# Sheet7.net
KiCad netlist of a schematic drawn in Altium Designer
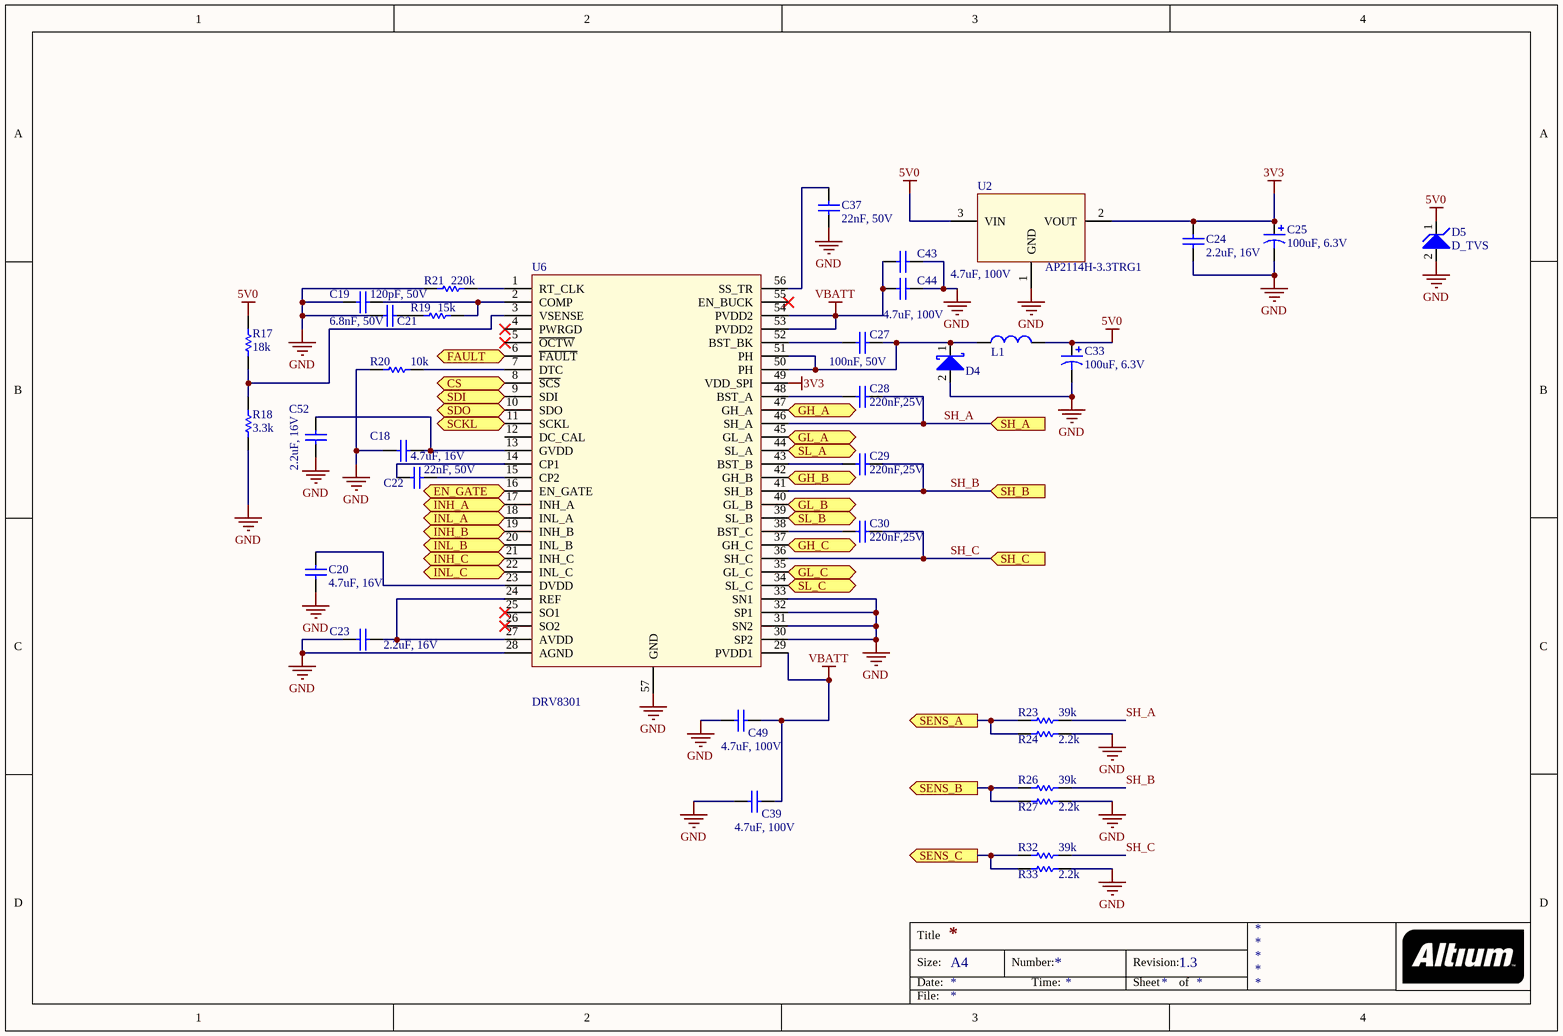
[diagram p0: Sheet7.SchDoc]

(export (version "E")
  (design (tool "Eeschema 10.0.6"))
  (components
    (comp (ref "C18")
      (value "4.7uF, 16V")
      (footprint "SMD-0603 Capacitor")
      (description "CAP 4.7u, 16V, 0603")
      (fields
        (field (name "MANUFACTURER PART NUMBER") "C1608X6S1C475K080AC")
        (field (name "MANUFACTURER") "TDK Corporation")
      )
      (libsource (lib "Master Data Link") (part "CAP"))
    )
    (comp (ref "C19")
      (value "120pF, 50V")
      (footprint "SMD-0603 Capacitor")
      (description "CAP 120p, 50V, 0603")
      (fields
        (field (name "MANUFACTURER PART NUMBER") "GRM39C121J50")
        (field (name "MANUFACTURER") "Murata Electronics North America")
      )
      (libsource (lib "Master Data Link") (part "CAP"))
    )
    (comp (ref "C20")
      (value "4.7uF, 16V")
      (footprint "SMD-0603 Capacitor")
      (description "CAP 4.7u, 16V, 0603")
      (fields
        (field (name "MANUFACTURER PART NUMBER") "C1608X6S1C475K080AC")
        (field (name "MANUFACTURER") "TDK Corporation")
      )
      (libsource (lib "Master Data Link") (part "CAP"))
    )
    (comp (ref "C21")
      (value "6.8nF, 50V")
      (footprint "SMD-0603 Capacitor")
      (description "CAP 6.8n, 50V, 0603")
      (fields
        (field (name "MANUFACTURER PART NUMBER") "GRM18R71H682KA01J")
        (field (name "MANUFACTURER") "Murata Electronics North America")
      )
      (libsource (lib "Master Data Link") (part "CAP"))
    )
    (comp (ref "C22")
      (value "22nF, 50V")
      (footprint "SMD-0603 Capacitor")
      (description "CAP 22n, 50V, 0603")
      (fields
        (field (name "MANUFACTURER PART NUMBER") "GRM18F51H223ZA01D")
        (field (name "MANUFACTURER") "Murata Electronics North America")
      )
      (libsource (lib "Master Data Link") (part "CAP"))
    )
    (comp (ref "C23")
      (value "2.2uF, 16V")
      (footprint "SMD-0603 Capacitor")
      (description "CAP 2.2u, 16V, 0603")
      (fields
        (field (name "MANUFACTURER PART NUMBER") "C1608X5R1C225M")
        (field (name "MANUFACTURER") "TDK Corporation")
      )
      (libsource (lib "Master Data Link") (part "CAP"))
    )
    (comp (ref "C24")
      (value "2.2uF, 16V")
      (footprint "SMD-0603 Capacitor")
      (description "CAP 2.2u, 16V, 0603")
      (fields
        (field (name "MANUFACTURER PART NUMBER") "C1608X5R1C225M")
        (field (name "MANUFACTURER") "TDK Corporation")
      )
      (libsource (lib "Master Data Link") (part "CAP"))
    )
    (comp (ref "C25")
      (value "100uF, 6.3V")
      (footprint "TANT B")
      (description "CAP 100u, 6.3V")
      (fields
        (field (name "MANUFACTURER PART NUMBER") "TPSB107K006R0400")
        (field (name "MANUFACTURER") "AVX Corporation")
      )
      (libsource (lib "Master Data Link") (part "CAP_POL"))
    )
    (comp (ref "C27")
      (value "100nF, 50V")
      (footprint "SMD-0603 Capacitor")
      (description "CAP 100n, 50V, 0603")
      (fields
        (field (name "MANUFACTURER PART NUMBER") "06035C104JAT2A")
        (field (name "MANUFACTURER") "AVX Corporation")
      )
      (libsource (lib "Master Data Link") (part "CAP"))
    )
    (comp (ref "C28")
      (value "220nF,25V")
      (footprint "SMD-0603 Capacitor")
      (description "CAP 220n, 25V, 0603")
      (fields
        (field (name "MANUFACTURER PART NUMBER") "TMK107B7224KA-T")
        (field (name "MANUFACTURER") "Taiyo Yuden")
      )
      (libsource (lib "Master Data Link") (part "CAP"))
    )
    (comp (ref "C29")
      (value "220nF,25V")
      (footprint "SMD-0603 Capacitor")
      (description "CAP 220n, 25V, 0603")
      (fields
        (field (name "MANUFACTURER PART NUMBER") "TMK107B7224KA-T")
        (field (name "MANUFACTURER") "Taiyo Yuden")
      )
      (libsource (lib "Master Data Link") (part "CAP"))
    )
    (comp (ref "C30")
      (value "220nF,25V")
      (footprint "SMD-0603 Capacitor")
      (description "CAP 220n, 25V, 0603")
      (fields
        (field (name "MANUFACTURER PART NUMBER") "TMK107B7224KA-T")
        (field (name "MANUFACTURER") "Taiyo Yuden")
      )
      (libsource (lib "Master Data Link") (part "CAP"))
    )
    (comp (ref "C33")
      (value "100uF, 6.3V")
      (footprint "TANT B")
      (description "CAP 100u, 6.3V")
      (fields
        (field (name "MANUFACTURER PART NUMBER") "TPSB107K006R0400")
        (field (name "MANUFACTURER") "AVX Corporation")
      )
      (libsource (lib "Master Data Link") (part "CAP_POL"))
    )
    (comp (ref "C37")
      (value "22nF, 50V")
      (footprint "SMD-0603 Capacitor")
      (description "CAP 22n, 50V, 0603")
      (fields
        (field (name "MANUFACTURER PART NUMBER") "GRM18F51H223ZA01D")
        (field (name "MANUFACTURER") "Murata Electronics North America")
      )
      (libsource (lib "Master Data Link") (part "CAP"))
    )
    (comp (ref "C39")
      (value "4.7uF, 100V")
      (footprint "SMD-1206 Capacitor")
      (description "4.7µF 100V Ceramic Capacitor X7S 1206")
      (fields
        (field (name "MANUFACTURER PART NUMBER") "12061Z475MAT2A")
        (field (name "MANUFACTURER") "AVX Corporation")
      )
      (libsource (lib "Master Data Link") (part "CAP"))
    )
    (comp (ref "C43")
      (value "4.7uF, 100V")
      (footprint "SMD-1206 Capacitor")
      (description "4.7µF 100V Ceramic Capacitor X7S 1206")
      (fields
        (field (name "MANUFACTURER PART NUMBER") "12061Z475MAT2A")
        (field (name "MANUFACTURER") "AVX Corporation")
      )
      (libsource (lib "Master Data Link") (part "CAP"))
    )
    (comp (ref "C44")
      (value "4.7uF, 100V")
      (footprint "SMD-1206 Capacitor")
      (description "4.7µF 100V Ceramic Capacitor X7S 1206")
      (fields
        (field (name "MANUFACTURER PART NUMBER") "12061Z475MAT2A")
        (field (name "MANUFACTURER") "AVX Corporation")
      )
      (libsource (lib "Master Data Link") (part "CAP"))
    )
    (comp (ref "C49")
      (value "4.7uF, 100V")
      (footprint "SMD-1206 Capacitor")
      (description "4.7µF 100V Ceramic Capacitor X7S 1206")
      (fields
        (field (name "MANUFACTURER PART NUMBER") "12061Z475MAT2A")
        (field (name "MANUFACTURER") "AVX Corporation")
      )
      (libsource (lib "Master Data Link") (part "CAP"))
    )
    (comp (ref "C52")
      (value "2.2uF, 16V")
      (footprint "SMD-0603 Capacitor")
      (description "CAP 2.2u, 16V, 0603")
      (fields
        (field (name "MANUFACTURER PART NUMBER") "C1608X5R1C225M")
        (field (name "MANUFACTURER") "TDK Corporation")
      )
      (libsource (lib "Master Data Link") (part "CAP"))
    )
    (comp (ref "D4")
      (value "Voltage and current important")
      (footprint "SOD-123W")
      (description "Shottky 60V 2A")
      (fields
        (field (name "MANUFACTURER PART NUMBER") "PMEG6020ER-115")
        (field (name "MANUFACTURER") "NXP Semiconductors")
      )
      (libsource (lib "Master Data Link") (part "D_SCHOTTKY"))
    )
    (comp (ref "D5")
      (value "D_TVS")
      (footprint "DO-214AC")
      (description "TVS diode 5V")
      (fields
        (field (name "MANUFACTURER PART NUMBER") "SMAJ5.0A")
        (field (name "MANUFACTURER") "Littelfuse Inc.")
      )
      (libsource (lib "Master Data Link") (part "D_TVS"))
    )
    (comp (ref "L1")
      (value "COIL")
      (footprint "HCM0503")
      (description "FIXED IND 22UH 1.9A 270 MOHM SMD")
      (fields (field (name "MANUFACTURER PART NUMBER") "HCM0503-220-R") (field (name "MANUFACTURER") "Eaton"))
      (libsource (lib "Master Data Link") (part "COIL"))
    )
    (comp (ref "R17")
      (value "18k")
      (footprint "SMD-0603 Resistor")
      (description "R 18k, 0603")
      (fields
        (field (name "MANUFACTURER PART NUMBER") "RK73H1JTTD1802F")
        (field (name "MANUFACTURER") "KOA Speer")
      )
      (libsource (lib "Master Data Link") (part "RES"))
    )
    (comp (ref "R18")
      (value "3.3k")
      (footprint "SMD-0603 Resistor")
      (description "R 3.3k, 0603")
      (fields
        (field (name "MANUFACTURER PART NUMBER") "RK73H1JTTD3301F")
        (field (name "MANUFACTURER") "KOA Speer")
      )
      (libsource (lib "Master Data Link") (part "RES"))
    )
    (comp (ref "R19")
      (value "15k")
      (footprint "SMD-0603 Resistor")
      (description "R 15k, 0603")
      (fields
        (field (name "MANUFACTURER PART NUMBER") "RK73H1JTTD1502F")
        (field (name "MANUFACTURER") "KOA Speer")
      )
      (libsource (lib "Master Data Link") (part "RES"))
    )
    (comp (ref "R20")
      (value "10k")
      (footprint "SMD-0603 Resistor")
      (description "R 10k, 0603")
      (fields
        (field (name "MANUFACTURER PART NUMBER") "RK73H1JTTD1002F")
        (field (name "MANUFACTURER") "KOA Speer")
      )
      (libsource (lib "Master Data Link") (part "RES"))
    )
    (comp (ref "R21")
      (value "220k")
      (footprint "SMD-0603 Resistor")
      (description "R 220k, 0603")
      (fields
        (field (name "MANUFACTURER PART NUMBER") "RK73H1JTTD2203F")
        (field (name "MANUFACTURER") "KOA Speer")
      )
      (libsource (lib "Master Data Link") (part "RES"))
    )
    (comp (ref "R23")
      (value "39k")
      (footprint "SMD-0603 Resistor")
      (description "R 39k, 0603")
      (fields
        (field (name "MANUFACTURER PART NUMBER") "ERJ-3EKF3902V")
        (field (name "MANUFACTURER") "Panasonic Electronic Components")
      )
      (libsource (lib "Master Data Link") (part "RES"))
    )
    (comp (ref "R24")
      (value "2.2k")
      (footprint "SMD-0603 Resistor")
      (description "R 2.2k, 0603")
      (fields
        (field (name "MANUFACTURER PART NUMBER") "RK73H1JTTD2201F")
        (field (name "MANUFACTURER") "KOA Speer")
      )
      (libsource (lib "Master Data Link") (part "RES"))
    )
    (comp (ref "R26")
      (value "39k")
      (footprint "SMD-0603 Resistor")
      (description "R 39k, 0603")
      (fields
        (field (name "MANUFACTURER PART NUMBER") "ERJ-3EKF3902V")
        (field (name "MANUFACTURER") "Panasonic Electronic Components")
      )
      (libsource (lib "Master Data Link") (part "RES"))
    )
    (comp (ref "R27")
      (value "2.2k")
      (footprint "SMD-0603 Resistor")
      (description "R 2.2k, 0603")
      (fields
        (field (name "MANUFACTURER PART NUMBER") "RK73H1JTTD2201F")
        (field (name "MANUFACTURER") "KOA Speer")
      )
      (libsource (lib "Master Data Link") (part "RES"))
    )
    (comp (ref "R32")
      (value "39k")
      (footprint "SMD-0603 Resistor")
      (description "R 39k, 0603")
      (fields
        (field (name "MANUFACTURER PART NUMBER") "ERJ-3EKF3902V")
        (field (name "MANUFACTURER") "Panasonic Electronic Components")
      )
      (libsource (lib "Master Data Link") (part "RES"))
    )
    (comp (ref "R33")
      (value "2.2k")
      (footprint "SMD-0603 Resistor")
      (description "R 2.2k, 0603")
      (fields
        (field (name "MANUFACTURER PART NUMBER") "RK73H1JTTD2201F")
        (field (name "MANUFACTURER") "KOA Speer")
      )
      (libsource (lib "Master Data Link") (part "RES"))
    )
    (comp (ref "U2")
      (value "3.3V")
      (footprint "SOT230P700X180-4N")
      (description "VREG LDO")
      (fields
        (field (name "MANUFACTURER PART NUMBER") "AP2114H-3.3TRG1")
        (field (name "MANUFACTURER") "Diodes Incorporated")
      )
      (libsource (lib "Master Data Link") (part "VREG_LDO"))
    )
    (comp (ref "U6")
      (value "DRV8301")
      (footprint "SOP127P600-8N")
      (description "IC MOTOR CONTROLLER SPI 56HTSSOP")
      (fields
        (field (name "MANUFACTURER PART NUMBER") "DRV8301DCA")
        (field (name "MANUFACTURER") "Texas Instruments")
      )
      (libsource (lib "Master Data Link") (part "DRV8301"))
    )
  )
  (nets
    (net (code "1") (name "/CS") (class "Default")
      (node (ref "U6") (pin "8") (pinfunction "~{SCS}_8") (pintype "passive"))
    )
    (net (code "2") (name "/EN_GATE") (class "Default")
      (node (ref "U6") (pin "16") (pinfunction "EN_GATE_16") (pintype "passive"))
    )
    (net (code "3") (name "/FAULT") (class "Default")
      (node (ref "U6") (pin "6") (pinfunction "~{FAULT}_6") (pintype "passive"))
    )
    (net (code "4") (name "/GH_A") (class "Default")
      (node (ref "U6") (pin "47") (pinfunction "GH_A_47") (pintype "passive"))
    )
    (net (code "5") (name "/GH_B") (class "Default")
      (node (ref "U6") (pin "42") (pinfunction "GH_B_42") (pintype "passive"))
    )
    (net (code "6") (name "/GH_C") (class "Default")
      (node (ref "U6") (pin "37") (pinfunction "GH_C_37") (pintype "passive"))
    )
    (net (code "7") (name "/GL_A") (class "Default")
      (node (ref "U6") (pin "45") (pinfunction "GL_A_45") (pintype "passive"))
    )
    (net (code "8") (name "/GL_B") (class "Default")
      (node (ref "U6") (pin "40") (pinfunction "GL_B_40") (pintype "passive"))
    )
    (net (code "9") (name "/GL_C") (class "Default")
      (node (ref "U6") (pin "35") (pinfunction "GL_C_35") (pintype "passive"))
    )
    (net (code "10") (name "/INH_A") (class "Default")
      (node (ref "U6") (pin "17") (pinfunction "INH_A_17") (pintype "passive"))
    )
    (net (code "11") (name "/INH_B") (class "Default")
      (node (ref "U6") (pin "19") (pinfunction "INH_B_19") (pintype "passive"))
    )
    (net (code "12") (name "/INH_C") (class "Default")
      (node (ref "U6") (pin "21") (pinfunction "INH_C_21") (pintype "passive"))
    )
    (net (code "13") (name "/INL_A") (class "Default")
      (node (ref "U6") (pin "18") (pinfunction "INL_A_18") (pintype "passive"))
    )
    (net (code "14") (name "/INL_B") (class "Default")
      (node (ref "U6") (pin "20") (pinfunction "INL_B_20") (pintype "passive"))
    )
    (net (code "15") (name "/INL_C") (class "Default")
      (node (ref "U6") (pin "22") (pinfunction "INL_C_22") (pintype "passive"))
    )
    (net (code "16") (name "/SCKL") (class "Default")
      (node (ref "U6") (pin "11") (pinfunction "SCKL_11") (pintype "passive"))
    )
    (net (code "17") (name "/SDI") (class "Default")
      (node (ref "U6") (pin "9") (pinfunction "SDI_9") (pintype "passive"))
    )
    (net (code "18") (name "/SDO") (class "Default")
      (node (ref "U6") (pin "10") (pinfunction "SDO_10") (pintype "passive"))
    )
    (net (code "19") (name "/SENS_A") (class "Default")
      (node (ref "R23") (pin "1") (pinfunction "1_1") (pintype "passive"))
      (node (ref "R24") (pin "1") (pinfunction "1_1") (pintype "passive"))
    )
    (net (code "20") (name "/SENS_B") (class "Default")
      (node (ref "R26") (pin "1") (pinfunction "1_1") (pintype "passive"))
      (node (ref "R27") (pin "1") (pinfunction "1_1") (pintype "passive"))
    )
    (net (code "21") (name "/SENS_C") (class "Default")
      (node (ref "R32") (pin "1") (pinfunction "1_1") (pintype "passive"))
      (node (ref "R33") (pin "1") (pinfunction "1_1") (pintype "passive"))
    )
    (net (code "22") (name "/SH_A") (class "Default")
      (node (ref "C28") (pin "2") (pinfunction "2_2") (pintype "passive"))
      (node (ref "R23") (pin "2") (pinfunction "2_2") (pintype "passive"))
      (node (ref "U6") (pin "46") (pinfunction "SH_A_46") (pintype "passive"))
    )
    (net (code "23") (name "/SH_B") (class "Default")
      (node (ref "C29") (pin "2") (pinfunction "2_2") (pintype "passive"))
      (node (ref "R26") (pin "2") (pinfunction "2_2") (pintype "passive"))
      (node (ref "U6") (pin "41") (pinfunction "SH_B_41") (pintype "passive"))
    )
    (net (code "24") (name "/SH_C") (class "Default")
      (node (ref "C30") (pin "2") (pinfunction "2_2") (pintype "passive"))
      (node (ref "R32") (pin "2") (pinfunction "2_2") (pintype "passive"))
      (node (ref "U6") (pin "36") (pinfunction "SH_C_36") (pintype "passive"))
    )
    (net (code "25") (name "/SL_A") (class "Default")
      (node (ref "U6") (pin "44") (pinfunction "SL_A_44") (pintype "passive"))
    )
    (net (code "26") (name "/SL_B") (class "Default")
      (node (ref "U6") (pin "39") (pinfunction "SL_B_39") (pintype "passive"))
    )
    (net (code "27") (name "/SL_C") (class "Default")
      (node (ref "U6") (pin "34") (pinfunction "SL_C_34") (pintype "passive"))
    )
    (net (code "28") (name "3V3") (class "Default")
      (node (ref "C24") (pin "2") (pinfunction "2_2") (pintype "passive"))
      (node (ref "C25") (pin "1") (pinfunction "1_1") (pintype "passive"))
      (node (ref "U2") (pin "2") (pinfunction "VOUT_2") (pintype "passive"))
      (node (ref "U6") (pin "49") (pinfunction "VDD_SPI_49") (pintype "passive"))
    )
    (net (code "29") (name "5V0") (class "Default")
      (node (ref "C33") (pin "1") (pinfunction "1_1") (pintype "passive"))
      (node (ref "D5") (pin "1") (pinfunction "K_1") (pintype "passive"))
      (node (ref "L1") (pin "2") (pinfunction "2_2") (pintype "passive"))
      (node (ref "R17") (pin "2") (pinfunction "2_2") (pintype "passive"))
      (node (ref "U2") (pin "3") (pinfunction "VIN_3") (pintype "passive"))
    )
    (net (code "30") (name "GND") (class "Default")
      (node (ref "C18") (pin "2") (pinfunction "2_2") (pintype "passive"))
      (node (ref "C19") (pin "1") (pinfunction "1_1") (pintype "passive"))
      (node (ref "C20") (pin "1") (pinfunction "1_1") (pintype "passive"))
      (node (ref "C21") (pin "1") (pinfunction "1_1") (pintype "passive"))
      (node (ref "C23") (pin "1") (pinfunction "1_1") (pintype "passive"))
      (node (ref "C24") (pin "1") (pinfunction "1_1") (pintype "passive"))
      (node (ref "C25") (pin "2") (pinfunction "2_2") (pintype "passive"))
      (node (ref "C33") (pin "2") (pinfunction "2_2") (pintype "passive"))
      (node (ref "C37") (pin "1") (pinfunction "1_1") (pintype "passive"))
      (node (ref "C39") (pin "2") (pinfunction "2_2") (pintype "passive"))
      (node (ref "C43") (pin "1") (pinfunction "1_1") (pintype "passive"))
      (node (ref "C44") (pin "1") (pinfunction "1_1") (pintype "passive"))
      (node (ref "C49") (pin "2") (pinfunction "2_2") (pintype "passive"))
      (node (ref "C52") (pin "1") (pinfunction "1_1") (pintype "passive"))
      (node (ref "D4") (pin "2") (pinfunction "A_2") (pintype "passive"))
      (node (ref "D5") (pin "2") (pinfunction "A_2") (pintype "passive"))
      (node (ref "R18") (pin "1") (pinfunction "1_1") (pintype "passive"))
      (node (ref "R20") (pin "1") (pinfunction "1_1") (pintype "passive"))
      (node (ref "R21") (pin "1") (pinfunction "1_1") (pintype "passive"))
      (node (ref "R24") (pin "2") (pinfunction "2_2") (pintype "passive"))
      (node (ref "R27") (pin "2") (pinfunction "2_2") (pintype "passive"))
      (node (ref "R33") (pin "2") (pinfunction "2_2") (pintype "passive"))
      (node (ref "U2") (pin "1") (pinfunction "GND_1") (pintype "passive"))
      (node (ref "U6") (pin "28") (pinfunction "AGND_28") (pintype "passive"))
      (node (ref "U6") (pin "30") (pinfunction "SP2_30") (pintype "passive"))
      (node (ref "U6") (pin "31") (pinfunction "SN2_31") (pintype "passive"))
      (node (ref "U6") (pin "32") (pinfunction "SP1_32") (pintype "passive"))
      (node (ref "U6") (pin "33") (pinfunction "SN1_33") (pintype "passive"))
      (node (ref "U6") (pin "57") (pinfunction "GND_57") (pintype "passive"))
    )
    (net (code "31") (name "Net-(C21-Pad2)") (class "Default")
      (node (ref "C21") (pin "2") (pinfunction "2_2") (pintype "passive"))
      (node (ref "R19") (pin "1") (pinfunction "1_1") (pintype "passive"))
    )
    (net (code "32") (name "Net-(D4-K)") (class "Default")
      (node (ref "C27") (pin "2") (pinfunction "2_2") (pintype "passive"))
      (node (ref "D4") (pin "1") (pinfunction "K_1") (pintype "passive"))
      (node (ref "L1") (pin "1") (pinfunction "1_1") (pintype "passive"))
      (node (ref "U6") (pin "50") (pinfunction "PH_50") (pintype "passive"))
      (node (ref "U6") (pin "51") (pinfunction "PH_51") (pintype "passive"))
    )
    (net (code "33") (name "Net-(U6-AVDD)") (class "Default")
      (node (ref "C23") (pin "2") (pinfunction "2_2") (pintype "passive"))
      (node (ref "U6") (pin "24") (pinfunction "REF_24") (pintype "passive"))
      (node (ref "U6") (pin "27") (pinfunction "AVDD_27") (pintype "passive"))
    )
    (net (code "34") (name "Net-(U6-BST_A)") (class "Default")
      (node (ref "C28") (pin "1") (pinfunction "1_1") (pintype "passive"))
      (node (ref "U6") (pin "48") (pinfunction "BST_A_48") (pintype "passive"))
    )
    (net (code "35") (name "Net-(U6-BST_B)") (class "Default")
      (node (ref "C29") (pin "1") (pinfunction "1_1") (pintype "passive"))
      (node (ref "U6") (pin "43") (pinfunction "BST_B_43") (pintype "passive"))
    )
    (net (code "36") (name "Net-(U6-BST_BK)") (class "Default")
      (node (ref "C27") (pin "1") (pinfunction "1_1") (pintype "passive"))
      (node (ref "U6") (pin "52") (pinfunction "BST_BK_52") (pintype "passive"))
    )
    (net (code "37") (name "Net-(U6-BST_C)") (class "Default")
      (node (ref "C30") (pin "1") (pinfunction "1_1") (pintype "passive"))
      (node (ref "U6") (pin "38") (pinfunction "BST_C_38") (pintype "passive"))
    )
    (net (code "38") (name "Net-(U6-COMP)") (class "Default")
      (node (ref "C19") (pin "2") (pinfunction "2_2") (pintype "passive"))
      (node (ref "R19") (pin "2") (pinfunction "2_2") (pintype "passive"))
      (node (ref "U6") (pin "2") (pinfunction "COMP_2") (pintype "passive"))
    )
    (net (code "39") (name "Net-(U6-CP1)") (class "Default")
      (node (ref "C22") (pin "1") (pinfunction "1_1") (pintype "passive"))
      (node (ref "U6") (pin "14") (pinfunction "CP1_14") (pintype "passive"))
    )
    (net (code "40") (name "Net-(U6-CP2)") (class "Default")
      (node (ref "C22") (pin "2") (pinfunction "2_2") (pintype "passive"))
      (node (ref "U6") (pin "15") (pinfunction "CP2_15") (pintype "passive"))
    )
    (net (code "41") (name "Net-(U6-DTC)") (class "Default")
      (node (ref "R20") (pin "2") (pinfunction "2_2") (pintype "passive"))
      (node (ref "U6") (pin "7") (pinfunction "DTC_7") (pintype "passive"))
    )
    (net (code "42") (name "Net-(U6-DVDD)") (class "Default")
      (node (ref "C20") (pin "2") (pinfunction "2_2") (pintype "passive"))
      (node (ref "U6") (pin "23") (pinfunction "DVDD_23") (pintype "passive"))
    )
    (net (code "43") (name "Net-(U6-GVDD)") (class "Default")
      (node (ref "C18") (pin "1") (pinfunction "1_1") (pintype "passive"))
      (node (ref "C52") (pin "2") (pinfunction "2_2") (pintype "passive"))
      (node (ref "U6") (pin "13") (pinfunction "GVDD_13") (pintype "passive"))
    )
    (net (code "44") (name "Net-(U6-RT_CLK)") (class "Default")
      (node (ref "R21") (pin "2") (pinfunction "2_2") (pintype "passive"))
      (node (ref "U6") (pin "1") (pinfunction "RT_CLK_1") (pintype "passive"))
    )
    (net (code "45") (name "Net-(U6-SS_TR)") (class "Default")
      (node (ref "C37") (pin "2") (pinfunction "2_2") (pintype "passive"))
      (node (ref "U6") (pin "56") (pinfunction "SS_TR_56") (pintype "passive"))
    )
    (net (code "46") (name "Net-(U6-VSENSE)") (class "Default")
      (node (ref "R17") (pin "1") (pinfunction "1_1") (pintype "passive"))
      (node (ref "R18") (pin "2") (pinfunction "2_2") (pintype "passive"))
      (node (ref "U6") (pin "3") (pinfunction "VSENSE_3") (pintype "passive"))
    )
    (net (code "47") (name "VBATT") (class "Default")
      (node (ref "C39") (pin "1") (pinfunction "1_1") (pintype "passive"))
      (node (ref "C43") (pin "2") (pinfunction "2_2") (pintype "passive"))
      (node (ref "C44") (pin "2") (pinfunction "2_2") (pintype "passive"))
      (node (ref "C49") (pin "1") (pinfunction "1_1") (pintype "passive"))
      (node (ref "U6") (pin "29") (pinfunction "PVDD1_29") (pintype "passive"))
      (node (ref "U6") (pin "53") (pinfunction "PVDD2_53") (pintype "passive"))
      (node (ref "U6") (pin "54") (pinfunction "PVDD2_54") (pintype "passive"))
    )
    (net (code "48") (name "unconnected-(U6-DC_CAL-Pad12)") (class "Default")
      (node (ref "U6") (pin "12") (pinfunction "DC_CAL_12") (pintype "passive"))
    )
    (net (code "49") (name "unconnected-(U6-EN_BUCK-Pad55)") (class "Default")
      (node (ref "U6") (pin "55") (pinfunction "EN_BUCK_55") (pintype "passive+no_connect"))
    )
    (net (code "50") (name "unconnected-(U6-PWRGD-Pad4)") (class "Default")
      (node (ref "U6") (pin "4") (pinfunction "PWRGD_4") (pintype "passive+no_connect"))
    )
    (net (code "51") (name "unconnected-(U6-SO1-Pad25)") (class "Default")
      (node (ref "U6") (pin "25") (pinfunction "SO1_25") (pintype "passive+no_connect"))
    )
    (net (code "52") (name "unconnected-(U6-SO2-Pad26)") (class "Default")
      (node (ref "U6") (pin "26") (pinfunction "SO2_26") (pintype "passive+no_connect"))
    )
    (net (code "53") (name "unconnected-(U6-~{OCTW}-Pad5)") (class "Default")
      (node (ref "U6") (pin "5") (pinfunction "~{OCTW}_5") (pintype "passive+no_connect"))
    )
  )
)
